# pwm.net
KiCad netlist of a schematic drawn in EAGLE
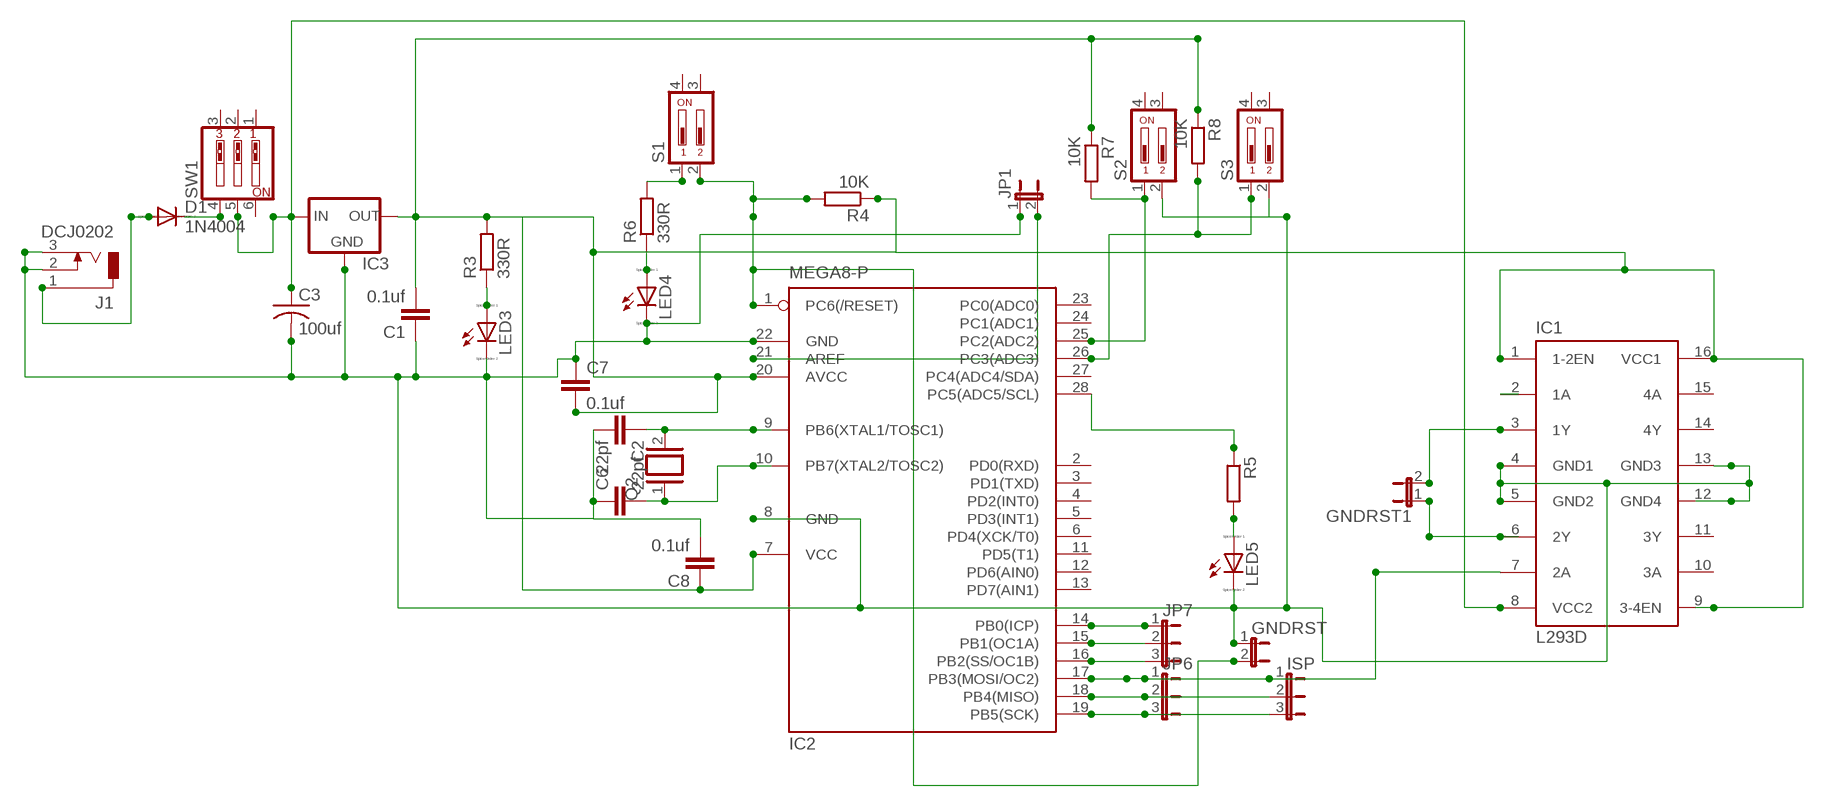
[diagram p0: schematic, sheet 1]

(export (version "E")
  (design (tool "Eeschema 10.0.6"))
  (components
    (comp (ref "C1")
      (value "0.1uf")
      (footprint "eagle-import:C2.5-3")
      (libsource (lib "eagle-import") (part "C2,5-3"))
    )
    (comp (ref "C2")
      (value "22pf")
      (footprint "eagle-import:C2.5-3")
      (libsource (lib "eagle-import") (part "C2,5-3"))
    )
    (comp (ref "C3")
      (value "100uf")
      (footprint "eagle-import:C025-025X050")
      (libsource (lib "eagle-import") (part "C-US025-025X050"))
    )
    (comp (ref "C6")
      (value "22pf")
      (footprint "eagle-import:C2.5-3")
      (libsource (lib "eagle-import") (part "C2,5-3"))
    )
    (comp (ref "C7")
      (value "0.1uf")
      (footprint "eagle-import:C2.5-3")
      (libsource (lib "eagle-import") (part "C2,5-3"))
    )
    (comp (ref "C8")
      (value "0.1uf")
      (footprint "eagle-import:C2.5-3")
      (libsource (lib "eagle-import") (part "C2,5-3"))
    )
    (comp (ref "D1")
      (value "1N4004")
      (footprint "eagle-import:DO41-10")
      (libsource (lib "eagle-import") (part "1N4004"))
    )
    (comp (ref "GNDRST")
      (value "JP1E")
      (footprint "eagle-import:JP1")
      (libsource (lib "eagle-import") (part "JP1E"))
    )
    (comp (ref "GNDRST1")
      (value "JP1E")
      (footprint "eagle-import:JP1")
      (libsource (lib "eagle-import") (part "JP1E"))
    )
    (comp (ref "IC1")
      (value "L293D")
      (footprint "eagle-import:DIL16")
      (libsource (lib "eagle-import") (part "L293D"))
    )
    (comp (ref "IC2")
      (value "MEGA8-P")
      (footprint "eagle-import:DIL28-3")
      (libsource (lib "eagle-import") (part "MEGA8-P"))
    )
    (comp (ref "IC3")
      (value "78XXS")
      (footprint "eagle-import:78XXS")
      (libsource (lib "eagle-import") (part "78XXS"))
    )
    (comp (ref "ISP")
      (value "JP2W")
      (footprint "eagle-import:JP2W")
      (libsource (lib "eagle-import") (part "JP2W"))
    )
    (comp (ref "J1")
      (value "DCJ0202")
      (footprint "eagle-import:DCJ0202")
      (libsource (lib "eagle-import") (part "DCJ0202"))
    )
    (comp (ref "JP1")
      (value "JP1E")
      (footprint "eagle-import:JP1")
      (libsource (lib "eagle-import") (part "JP1E"))
    )
    (comp (ref "JP6")
      (value "JP2W")
      (footprint "eagle-import:JP2W")
      (libsource (lib "eagle-import") (part "JP2W"))
    )
    (comp (ref "JP7")
      (value "JP2W")
      (footprint "eagle-import:JP2W")
      (libsource (lib "eagle-import") (part "JP2W"))
    )
    (comp (ref "LED3")
      (value "LED_ELD260")
      (footprint "eagle-import:LED_LD260")
      (libsource (lib "eagle-import") (part "LED_ELD260"))
    )
    (comp (ref "LED4")
      (value "LED_ELD260")
      (footprint "eagle-import:LED_LD260")
      (libsource (lib "eagle-import") (part "LED_ELD260"))
    )
    (comp (ref "LED5")
      (value "LED_ELD260")
      (footprint "eagle-import:LED_LD260")
      (libsource (lib "eagle-import") (part "LED_ELD260"))
    )
    (comp (ref "Q2")
      (value "XTAL/S")
      (footprint "eagle-import:QS")
      (libsource (lib "eagle-import") (part "XTAL/S"))
    )
    (comp (ref "R3")
      (value "330R")
      (footprint "eagle-import:0207_7")
      (libsource (lib "eagle-import") (part "R-EU_0207/7"))
    )
    (comp (ref "R4")
      (value "10K")
      (footprint "eagle-import:0207_7")
      (libsource (lib "eagle-import") (part "R-EU_0207/7"))
    )
    (comp (ref "R5")
      (value "R-EU_0207/7")
      (footprint "eagle-import:0207_7")
      (libsource (lib "eagle-import") (part "R-EU_0207/7"))
    )
    (comp (ref "R6")
      (value "330R")
      (footprint "eagle-import:0207_7")
      (libsource (lib "eagle-import") (part "R-EU_0207/7"))
    )
    (comp (ref "R7")
      (value "10K")
      (footprint "eagle-import:0207_7")
      (libsource (lib "eagle-import") (part "R-EU_0207/7"))
    )
    (comp (ref "R8")
      (value "10K")
      (footprint "eagle-import:0207_7")
      (libsource (lib "eagle-import") (part "R-EU_0207/7"))
    )
    (comp (ref "S1")
      (value "SD4-02")
      (footprint "eagle-import:SD4-02")
      (libsource (lib "eagle-import") (part "SD4-02"))
    )
    (comp (ref "S2")
      (value "SD4-02")
      (footprint "eagle-import:SD4-02")
      (libsource (lib "eagle-import") (part "SD4-02"))
    )
    (comp (ref "S3")
      (value "SD4-02")
      (footprint "eagle-import:SD4-02")
      (libsource (lib "eagle-import") (part "SD4-02"))
    )
    (comp (ref "SW1")
      (value "SW_DIP-3")
      (footprint "eagle-import:EDG-03")
      (libsource (lib "eagle-import") (part "SW_DIP-3"))
    )
  )
  (nets
    (net (code "1") (name "/GND4") (class "Default")
      (node (ref "IC1") (pin "12") (pinfunction "GND4_12") (pintype "power_in"))
    )
    (net (code "2") (name "Net-(D1-PadA)") (class "Default")
      (node (ref "D1") (pin "A") (pinfunction "A_A") (pintype "passive"))
      (node (ref "J1") (pin "1") (pinfunction "1_1") (pintype "passive"))
    )
    (net (code "3") (name "Net-(D1-PadC)") (class "Default")
      (node (ref "D1") (pin "C") (pinfunction "C_C") (pintype "passive"))
      (node (ref "SW1") (pin "4") (pinfunction "4_4") (pintype "passive"))
    )
    (net (code "4") (name "Net-(IC1-1-2EN)") (class "Default")
      (node (ref "C1") (pin "2") (pinfunction "2_2") (pintype "passive"))
      (node (ref "C7") (pin "2") (pinfunction "2_2") (pintype "passive"))
      (node (ref "C8") (pin "1") (pinfunction "1_1") (pintype "passive"))
      (node (ref "IC1") (pin "1") (pinfunction "1-2EN_1") (pintype "input"))
      (node (ref "IC1") (pin "16") (pinfunction "VCC1_16") (pintype "power_in"))
      (node (ref "IC1") (pin "9") (pinfunction "3-4EN_9") (pintype "input"))
      (node (ref "IC2") (pin "20") (pinfunction "AVCC_20") (pintype "power_in"))
      (node (ref "IC2") (pin "7") (pinfunction "VCC_7") (pintype "power_in"))
      (node (ref "IC3") (pin "OUT") (pinfunction "OUT_OUT") (pintype "passive"))
      (node (ref "R3") (pin "2") (pinfunction "2_2") (pintype "passive"))
      (node (ref "R4") (pin "1") (pinfunction "1_1") (pintype "passive"))
      (node (ref "R7") (pin "1") (pinfunction "1_1") (pintype "passive"))
      (node (ref "R8") (pin "1") (pinfunction "1_1") (pintype "passive"))
    )
    (net (code "5") (name "Net-(IC1-1Y)") (class "Default")
      (node (ref "GNDRST1") (pin "2") (pinfunction "2_2") (pintype "passive"))
      (node (ref "IC1") (pin "3") (pinfunction "1Y_3") (pintype "output"))
    )
    (net (code "6") (name "Net-(IC1-2A)") (class "Default")
      (node (ref "IC1") (pin "7") (pinfunction "2A_7") (pintype "input"))
      (node (ref "IC2") (pin "17") (pinfunction "PB3(MOSI/OC2)_17") (pintype "bidirectional"))
      (node (ref "ISP") (pin "1") (pinfunction "1_1") (pintype "passive"))
      (node (ref "JP6") (pin "1") (pinfunction "1_1") (pintype "passive"))
    )
    (net (code "7") (name "Net-(IC1-2Y)") (class "Default")
      (node (ref "GNDRST1") (pin "1") (pinfunction "1_1") (pintype "passive"))
      (node (ref "IC1") (pin "6") (pinfunction "2Y_6") (pintype "output"))
    )
    (net (code "8") (name "Net-(IC1-GND1)") (class "Default")
      (node (ref "C1") (pin "1") (pinfunction "1_1") (pintype "passive"))
      (node (ref "C2") (pin "2") (pinfunction "2_2") (pintype "passive"))
      (node (ref "C3") (pin "2") (pinfunction "2_2") (pintype "passive"))
      (node (ref "C6") (pin "1") (pinfunction "1_1") (pintype "passive"))
      (node (ref "C7") (pin "1") (pinfunction "1_1") (pintype "passive"))
      (node (ref "C8") (pin "2") (pinfunction "2_2") (pintype "passive"))
      (node (ref "GNDRST") (pin "1") (pinfunction "1_1") (pintype "passive"))
      (node (ref "IC1") (pin "13") (pinfunction "GND3_13") (pintype "power_in"))
      (node (ref "IC1") (pin "4") (pinfunction "GND1_4") (pintype "power_in"))
      (node (ref "IC1") (pin "5") (pinfunction "GND2_5") (pintype "power_in"))
      (node (ref "IC2") (pin "22") (pinfunction "GND_22") (pintype "power_in"))
      (node (ref "IC2") (pin "8") (pinfunction "GND_8") (pintype "power_in"))
      (node (ref "IC3") (pin "GND") (pinfunction "GND_GND") (pintype "input"))
      (node (ref "J1") (pin "2") (pinfunction "2_2") (pintype "passive"))
      (node (ref "J1") (pin "3") (pinfunction "3_3") (pintype "passive"))
      (node (ref "JP1") (pin "1") (pinfunction "1_1") (pintype "passive"))
      (node (ref "LED3") (pin "K") (pinfunction "C_K") (pintype "passive"))
      (node (ref "LED4") (pin "K") (pinfunction "C_K") (pintype "passive"))
      (node (ref "LED5") (pin "K") (pinfunction "C_K") (pintype "passive"))
      (node (ref "S2") (pin "2") (pinfunction "2_2") (pintype "passive"))
      (node (ref "S3") (pin "2") (pinfunction "2_2") (pintype "passive"))
    )
    (net (code "9") (name "Net-(IC1-VCC2)") (class "Default")
      (node (ref "C3") (pin "1") (pinfunction "1_1") (pintype "passive"))
      (node (ref "IC1") (pin "8") (pinfunction "VCC2_8") (pintype "power_in"))
      (node (ref "IC3") (pin "IN") (pinfunction "IN_IN") (pintype "input"))
      (node (ref "SW1") (pin "5") (pinfunction "5_5") (pintype "passive"))
    )
    (net (code "10") (name "Net-(IC2-AREF)") (class "Default")
      (node (ref "IC2") (pin "21") (pinfunction "AREF_21") (pintype "passive"))
      (node (ref "JP1") (pin "2") (pinfunction "2_2") (pintype "passive"))
    )
    (net (code "11") (name "Net-(IC2-PB0(ICP))") (class "Default")
      (node (ref "IC2") (pin "14") (pinfunction "PB0(ICP)_14") (pintype "bidirectional"))
      (node (ref "JP7") (pin "1") (pinfunction "1_1") (pintype "passive"))
    )
    (net (code "12") (name "Net-(IC2-PB1(OC1A))") (class "Default")
      (node (ref "IC2") (pin "15") (pinfunction "PB1(OC1A)_15") (pintype "bidirectional"))
      (node (ref "JP7") (pin "2") (pinfunction "2_2") (pintype "passive"))
    )
    (net (code "13") (name "Net-(IC2-PB2(SS{slash}OC1B))") (class "Default")
      (node (ref "IC2") (pin "16") (pinfunction "PB2(SS/OC1B)_16") (pintype "bidirectional"))
      (node (ref "JP7") (pin "3") (pinfunction "3_3") (pintype "passive"))
    )
    (net (code "14") (name "Net-(IC2-PB4(MISO))") (class "Default")
      (node (ref "IC2") (pin "18") (pinfunction "PB4(MISO)_18") (pintype "bidirectional"))
      (node (ref "ISP") (pin "2") (pinfunction "2_2") (pintype "passive"))
      (node (ref "JP6") (pin "2") (pinfunction "2_2") (pintype "passive"))
    )
    (net (code "15") (name "Net-(IC2-PB5(SCK))") (class "Default")
      (node (ref "IC2") (pin "19") (pinfunction "PB5(SCK)_19") (pintype "bidirectional"))
      (node (ref "ISP") (pin "3") (pinfunction "3_3") (pintype "passive"))
      (node (ref "JP6") (pin "3") (pinfunction "3_3") (pintype "passive"))
    )
    (net (code "16") (name "Net-(IC2-PB6(XTAL1{slash}TOSC1))") (class "Default")
      (node (ref "C2") (pin "1") (pinfunction "1_1") (pintype "passive"))
      (node (ref "IC2") (pin "9") (pinfunction "PB6(XTAL1/TOSC1)_9") (pintype "bidirectional"))
      (node (ref "Q2") (pin "2") (pinfunction "2_2") (pintype "passive"))
    )
    (net (code "17") (name "Net-(IC2-PB7(XTAL2{slash}TOSC2))") (class "Default")
      (node (ref "C6") (pin "2") (pinfunction "2_2") (pintype "passive"))
      (node (ref "IC2") (pin "10") (pinfunction "PB7(XTAL2/TOSC2)_10") (pintype "bidirectional"))
      (node (ref "Q2") (pin "1") (pinfunction "1_1") (pintype "passive"))
    )
    (net (code "18") (name "Net-(IC2-PC2(ADC2))") (class "Default")
      (node (ref "IC2") (pin "25") (pinfunction "PC2(ADC2)_25") (pintype "bidirectional"))
      (node (ref "R7") (pin "2") (pinfunction "2_2") (pintype "passive"))
      (node (ref "S2") (pin "1") (pinfunction "1_1") (pintype "passive"))
    )
    (net (code "19") (name "Net-(IC2-PC3(ADC3))") (class "Default")
      (node (ref "IC2") (pin "26") (pinfunction "PC3(ADC3)_26") (pintype "bidirectional"))
      (node (ref "R8") (pin "2") (pinfunction "2_2") (pintype "passive"))
      (node (ref "S3") (pin "1") (pinfunction "1_1") (pintype "passive"))
    )
    (net (code "20") (name "Net-(IC2-PC5(ADC5{slash}SCL))") (class "Default")
      (node (ref "IC2") (pin "28") (pinfunction "PC5(ADC5/SCL)_28") (pintype "bidirectional"))
      (node (ref "R5") (pin "1") (pinfunction "1_1") (pintype "passive"))
    )
    (net (code "21") (name "Net-(IC2-PC6({slash}RESET))") (class "Default")
      (node (ref "GNDRST") (pin "2") (pinfunction "2_2") (pintype "passive"))
      (node (ref "IC2") (pin "1") (pinfunction "PC6(/RESET)_1") (pintype "bidirectional"))
      (node (ref "R4") (pin "2") (pinfunction "2_2") (pintype "passive"))
      (node (ref "S1") (pin "2") (pinfunction "2_2") (pintype "passive"))
    )
    (net (code "22") (name "Net-(LED3-PadA)") (class "Default")
      (node (ref "LED3") (pin "A") (pinfunction "A_A") (pintype "passive"))
      (node (ref "R3") (pin "1") (pinfunction "1_1") (pintype "passive"))
    )
    (net (code "23") (name "Net-(LED4-PadA)") (class "Default")
      (node (ref "LED4") (pin "A") (pinfunction "A_A") (pintype "passive"))
      (node (ref "R6") (pin "1") (pinfunction "1_1") (pintype "passive"))
    )
    (net (code "24") (name "Net-(LED5-PadA)") (class "Default")
      (node (ref "LED5") (pin "A") (pinfunction "A_A") (pintype "passive"))
      (node (ref "R5") (pin "2") (pinfunction "2_2") (pintype "passive"))
    )
    (net (code "25") (name "Net-(R6-Pad2)") (class "Default")
      (node (ref "R6") (pin "2") (pinfunction "2_2") (pintype "passive"))
      (node (ref "S1") (pin "1") (pinfunction "1_1") (pintype "passive"))
    )
    (net (code "26") (name "unconnected-(IC1-1A-Pad2)") (class "Default")
      (node (ref "IC1") (pin "2") (pinfunction "1A_2") (pintype "input"))
    )
    (net (code "27") (name "unconnected-(IC1-3A-Pad10)") (class "Default")
      (node (ref "IC1") (pin "10") (pinfunction "3A_10") (pintype "input"))
    )
    (net (code "28") (name "unconnected-(IC1-3Y-Pad11)") (class "Default")
      (node (ref "IC1") (pin "11") (pinfunction "3Y_11") (pintype "output"))
    )
    (net (code "29") (name "unconnected-(IC1-4A-Pad15)") (class "Default")
      (node (ref "IC1") (pin "15") (pinfunction "4A_15") (pintype "input"))
    )
    (net (code "30") (name "unconnected-(IC1-4Y-Pad14)") (class "Default")
      (node (ref "IC1") (pin "14") (pinfunction "4Y_14") (pintype "output"))
    )
    (net (code "31") (name "unconnected-(IC2-PC0(ADC0)-Pad23)") (class "Default")
      (node (ref "IC2") (pin "23") (pinfunction "PC0(ADC0)_23") (pintype "bidirectional"))
    )
    (net (code "32") (name "unconnected-(IC2-PC1(ADC1)-Pad24)") (class "Default")
      (node (ref "IC2") (pin "24") (pinfunction "PC1(ADC1)_24") (pintype "bidirectional"))
    )
    (net (code "33") (name "unconnected-(IC2-PC4(ADC4{slash}SDA)-Pad27)") (class "Default")
      (node (ref "IC2") (pin "27") (pinfunction "PC4(ADC4/SDA)_27") (pintype "bidirectional"))
    )
    (net (code "34") (name "unconnected-(IC2-PD0(RXD)-Pad2)") (class "Default")
      (node (ref "IC2") (pin "2") (pinfunction "PD0(RXD)_2") (pintype "bidirectional"))
    )
    (net (code "35") (name "unconnected-(IC2-PD1(TXD)-Pad3)") (class "Default")
      (node (ref "IC2") (pin "3") (pinfunction "PD1(TXD)_3") (pintype "bidirectional"))
    )
    (net (code "36") (name "unconnected-(IC2-PD2(INT0)-Pad4)") (class "Default")
      (node (ref "IC2") (pin "4") (pinfunction "PD2(INT0)_4") (pintype "bidirectional"))
    )
    (net (code "37") (name "unconnected-(IC2-PD3(INT1)-Pad5)") (class "Default")
      (node (ref "IC2") (pin "5") (pinfunction "PD3(INT1)_5") (pintype "bidirectional"))
    )
    (net (code "38") (name "unconnected-(IC2-PD4(XCK{slash}T0)-Pad6)") (class "Default")
      (node (ref "IC2") (pin "6") (pinfunction "PD4(XCK/T0)_6") (pintype "bidirectional"))
    )
    (net (code "39") (name "unconnected-(IC2-PD5(T1)-Pad11)") (class "Default")
      (node (ref "IC2") (pin "11") (pinfunction "PD5(T1)_11") (pintype "bidirectional"))
    )
    (net (code "40") (name "unconnected-(IC2-PD6(AIN0)-Pad12)") (class "Default")
      (node (ref "IC2") (pin "12") (pinfunction "PD6(AIN0)_12") (pintype "bidirectional"))
    )
    (net (code "41") (name "unconnected-(IC2-PD7(AIN1)-Pad13)") (class "Default")
      (node (ref "IC2") (pin "13") (pinfunction "PD7(AIN1)_13") (pintype "bidirectional"))
    )
    (net (code "42") (name "unconnected-(S1-Pad3)") (class "Default")
      (node (ref "S1") (pin "3") (pinfunction "3_3") (pintype "passive"))
    )
    (net (code "43") (name "unconnected-(S1-Pad4)") (class "Default")
      (node (ref "S1") (pin "4") (pinfunction "4_4") (pintype "passive"))
    )
    (net (code "44") (name "unconnected-(S2-Pad3)") (class "Default")
      (node (ref "S2") (pin "3") (pinfunction "3_3") (pintype "passive"))
    )
    (net (code "45") (name "unconnected-(S2-Pad4)") (class "Default")
      (node (ref "S2") (pin "4") (pinfunction "4_4") (pintype "passive"))
    )
    (net (code "46") (name "unconnected-(S3-Pad3)") (class "Default")
      (node (ref "S3") (pin "3") (pinfunction "3_3") (pintype "passive"))
    )
    (net (code "47") (name "unconnected-(S3-Pad4)") (class "Default")
      (node (ref "S3") (pin "4") (pinfunction "4_4") (pintype "passive"))
    )
    (net (code "48") (name "unconnected-(SW1-Pad1)") (class "Default")
      (node (ref "SW1") (pin "1") (pinfunction "1_1") (pintype "passive"))
    )
    (net (code "49") (name "unconnected-(SW1-Pad2)") (class "Default")
      (node (ref "SW1") (pin "2") (pinfunction "2_2") (pintype "passive"))
    )
    (net (code "50") (name "unconnected-(SW1-Pad3)") (class "Default")
      (node (ref "SW1") (pin "3") (pinfunction "3_3") (pintype "passive"))
    )
    (net (code "51") (name "unconnected-(SW1-Pad6)") (class "Default")
      (node (ref "SW1") (pin "6") (pinfunction "6_6") (pintype "passive"))
    )
  )
)
